# 2021_ZT_1.net
KiCad netlist of a schematic drawn in EasyEDA Pro
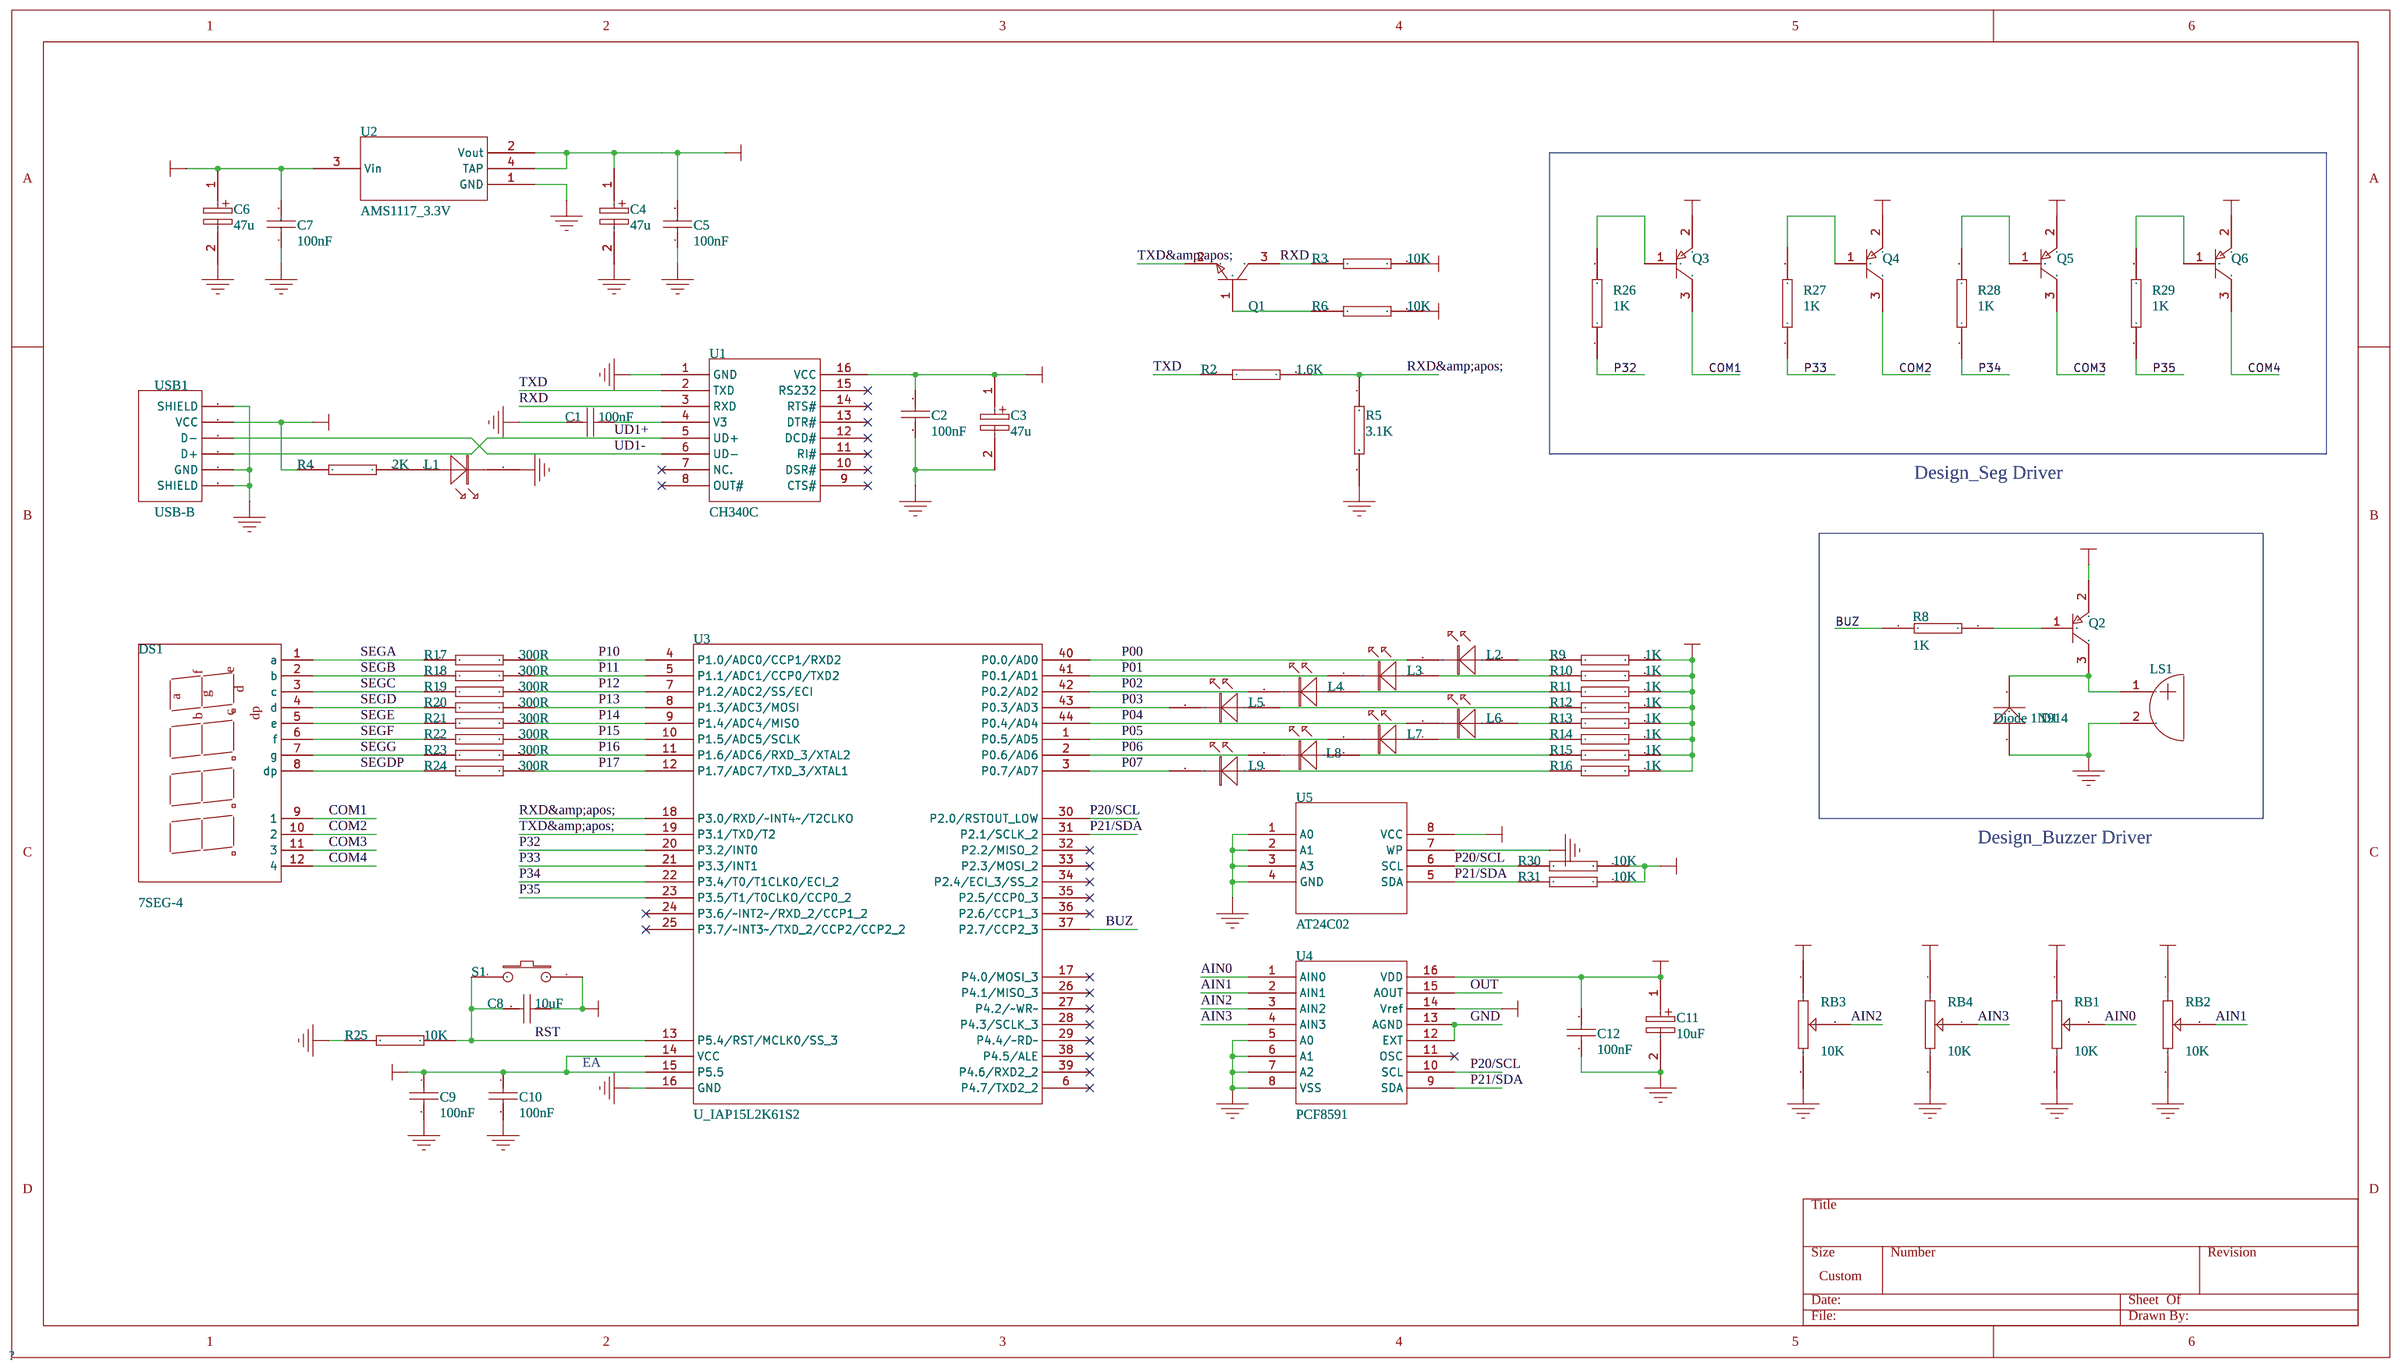
[diagram p0: schematic sheet]

(export (version "E")
  (design (tool "Eeschema 10.0.6"))
  (components
    (comp (ref "C1") (value "100nF") (libsource (lib "easyedapro") (part "CAP")))
    (comp (ref "C2") (value "100nF") (libsource (lib "easyedapro") (part "CAP")))
    (comp (ref "C3")
      (value "47u")
      (description "Electrolytic Capacitor")
      (libsource (lib "easyedapro") (part "CAP-2"))
    )
    (comp (ref "C4")
      (value "47u")
      (description "Electrolytic Capacitor")
      (libsource (lib "easyedapro") (part "CAP-2"))
    )
    (comp (ref "C5") (value "100nF") (description "Capacitor") (libsource (lib "easyedapro") (part "C_CAP")))
    (comp (ref "C6")
      (value "47u")
      (description "Electrolytic Capacitor")
      (libsource (lib "easyedapro") (part "CAP-2"))
    )
    (comp (ref "C7") (value "100nF") (description "Capacitor") (libsource (lib "easyedapro") (part "C_CAP")))
    (comp (ref "C8") (value "10uF") (libsource (lib "easyedapro") (part "CAP")))
    (comp (ref "C9") (value "100nF") (libsource (lib "easyedapro") (part "CAP")))
    (comp (ref "C10") (value "100nF") (libsource (lib "easyedapro") (part "CAP")))
    (comp (ref "C11")
      (value "10uF")
      (description "Electrolytic Capacitor")
      (libsource (lib "easyedapro") (part "ELECTRO2"))
    )
    (comp (ref "C12") (value "100nF") (description "Capacitor") (libsource (lib "easyedapro") (part "CAP")))
    (comp (ref "D1")
      (value "Diode 1N914")
      (description "High Conductance Fast Diode")
      (libsource (lib "easyedapro") (part "Diode 1N914"))
    )
    (comp (ref "DS1")
      (value "7SEG-4")
      (description "4 Seven-Segment Display, Right Hand Decimal")
      (libsource (lib "easyedapro") (part "7SEG-4"))
    )
    (comp (ref "L1") (value "LED") (libsource (lib "easyedapro") (part "LED")))
    (comp (ref "L2") (value "LED") (libsource (lib "easyedapro") (part "LED")))
    (comp (ref "L3") (value "LED") (libsource (lib "easyedapro") (part "LED")))
    (comp (ref "L4") (value "LED") (libsource (lib "easyedapro") (part "LED")))
    (comp (ref "L5") (value "LED") (libsource (lib "easyedapro") (part "LED")))
    (comp (ref "L6") (value "LED") (libsource (lib "easyedapro") (part "LED")))
    (comp (ref "L7") (value "LED") (libsource (lib "easyedapro") (part "LED")))
    (comp (ref "L8") (value "LED") (libsource (lib "easyedapro") (part "LED")))
    (comp (ref "L9") (value "LED") (libsource (lib "easyedapro") (part "LED")))
    (comp (ref "LS1") (value "S_BUZZER") (libsource (lib "easyedapro") (part "S_BUZZER")))
    (comp (ref "Q1")
      (value "8050-SOT23")
      (description "PNP-S8050")
      (libsource (lib "easyedapro") (part "Q_NPN"))
    )
    (comp (ref "Q2")
      (value "2N3906")
      (description "PNP General Purpose Amplifier")
      (libsource (lib "easyedapro") (part "2N3906"))
    )
    (comp (ref "Q3")
      (value "2N3906")
      (description "PNP General Purpose Amplifier")
      (libsource (lib "easyedapro") (part "2N3906"))
    )
    (comp (ref "Q4")
      (value "2N3906")
      (description "PNP General Purpose Amplifier")
      (libsource (lib "easyedapro") (part "2N3906"))
    )
    (comp (ref "Q5")
      (value "2N3906")
      (description "PNP General Purpose Amplifier")
      (libsource (lib "easyedapro") (part "2N3906"))
    )
    (comp (ref "Q6")
      (value "2N3906")
      (description "PNP General Purpose Amplifier")
      (libsource (lib "easyedapro") (part "2N3906"))
    )
    (comp (ref "R2") (value "1.6K") (libsource (lib "easyedapro") (part "RES2")))
    (comp (ref "R3") (value "10K") (libsource (lib "easyedapro") (part "RES2")))
    (comp (ref "R4") (value "2K") (libsource (lib "easyedapro") (part "RES2")))
    (comp (ref "R5") (value "3.1K") (libsource (lib "easyedapro") (part "RES2")))
    (comp (ref "R6") (value "10K") (libsource (lib "easyedapro") (part "RES2")))
    (comp (ref "R8") (value "1K") (libsource (lib "easyedapro") (part "RES2")))
    (comp (ref "R9") (value "1K") (libsource (lib "easyedapro") (part "RES2")))
    (comp (ref "R10") (value "1K") (libsource (lib "easyedapro") (part "RES2")))
    (comp (ref "R11") (value "1K") (libsource (lib "easyedapro") (part "RES2")))
    (comp (ref "R12") (value "1K") (libsource (lib "easyedapro") (part "RES2")))
    (comp (ref "R13") (value "1K") (libsource (lib "easyedapro") (part "RES2")))
    (comp (ref "R14") (value "1K") (libsource (lib "easyedapro") (part "RES2")))
    (comp (ref "R15") (value "1K") (libsource (lib "easyedapro") (part "RES2")))
    (comp (ref "R16") (value "1K") (libsource (lib "easyedapro") (part "RES2")))
    (comp (ref "R17") (value "300R") (libsource (lib "easyedapro") (part "RES2")))
    (comp (ref "R18") (value "300R") (libsource (lib "easyedapro") (part "RES2")))
    (comp (ref "R19") (value "300R") (libsource (lib "easyedapro") (part "RES2")))
    (comp (ref "R20") (value "300R") (libsource (lib "easyedapro") (part "RES2")))
    (comp (ref "R21") (value "300R") (libsource (lib "easyedapro") (part "RES2")))
    (comp (ref "R22") (value "300R") (libsource (lib "easyedapro") (part "RES2")))
    (comp (ref "R23") (value "300R") (libsource (lib "easyedapro") (part "RES2")))
    (comp (ref "R24") (value "300R") (libsource (lib "easyedapro") (part "RES2")))
    (comp (ref "R25") (value "10K") (libsource (lib "easyedapro") (part "RES2")))
    (comp (ref "R26") (value "1K") (libsource (lib "easyedapro") (part "RES2")))
    (comp (ref "R27") (value "1K") (libsource (lib "easyedapro") (part "RES2")))
    (comp (ref "R28") (value "1K") (libsource (lib "easyedapro") (part "RES2")))
    (comp (ref "R29") (value "1K") (libsource (lib "easyedapro") (part "RES2")))
    (comp (ref "R30") (value "10K") (libsource (lib "easyedapro") (part "RES2")))
    (comp (ref "R31") (value "10K") (libsource (lib "easyedapro") (part "RES2")))
    (comp (ref "RB1")
      (value "10K")
      (description "Potentiometer")
      (libsource (lib "easyedapro") (part "POT2"))
    )
    (comp (ref "RB2")
      (value "10K")
      (description "Potentiometer")
      (libsource (lib "easyedapro") (part "POT2"))
    )
    (comp (ref "RB3")
      (value "10K")
      (description "Potentiometer")
      (libsource (lib "easyedapro") (part "POT2"))
    )
    (comp (ref "RB4")
      (value "10K")
      (description "Potentiometer")
      (libsource (lib "easyedapro") (part "POT2"))
    )
    (comp (ref "S1") (value "SW-PB") (libsource (lib "easyedapro") (part "SW-PB")))
    (comp (ref "U1") (value "CH340C") (libsource (lib "easyedapro") (part "CH340C")))
    (comp (ref "U2")
      (value "AMS1117_3.3V")
      (description "POWER")
      (libsource (lib "easyedapro") (part "U_ASM1117"))
    )
    (comp (ref "U3")
      (value "U_IAP15L2K61S2")
      (description "MCU")
      (libsource (lib "easyedapro") (part "U_IAP15F2K61S2"))
    )
    (comp (ref "U4") (value "PCF8591") (libsource (lib "easyedapro") (part "PCF8591")))
    (comp (ref "U5") (value "AT24C02") (libsource (lib "easyedapro") (part "AT24C02")))
    (comp (ref "USB1")
      (value "USB-B")
      (description "Connector")
      (libsource (lib "easyedapro") (part "USB_A"))
    )
  )
  (nets
    (net (code "1") (name "+3V3") (class "Default")
      (node (ref "C10") (pin "1") (pintype "input"))
      (node (ref "C11") (pin "1") (pinfunction "1_1") (pintype "input"))
      (node (ref "C12") (pin "2") (pintype "input"))
      (node (ref "C4") (pin "1") (pinfunction "1_1") (pintype "input"))
      (node (ref "C5") (pin "2") (pinfunction "2_2") (pintype "input"))
      (node (ref "C8") (pin "2") (pintype "input"))
      (node (ref "C9") (pin "1") (pintype "input"))
      (node (ref "Q2") (pin "2") (pinfunction "E_2") (pintype "input"))
      (node (ref "Q3") (pin "2") (pinfunction "E_2") (pintype "input"))
      (node (ref "Q4") (pin "2") (pinfunction "E_2") (pintype "input"))
      (node (ref "Q5") (pin "2") (pinfunction "E_2") (pintype "input"))
      (node (ref "Q6") (pin "2") (pinfunction "E_2") (pintype "input"))
      (node (ref "R10") (pin "2") (pinfunction "2_2") (pintype "input"))
      (node (ref "R11") (pin "2") (pinfunction "2_2") (pintype "input"))
      (node (ref "R12") (pin "2") (pinfunction "2_2") (pintype "input"))
      (node (ref "R13") (pin "2") (pinfunction "2_2") (pintype "input"))
      (node (ref "R14") (pin "2") (pinfunction "2_2") (pintype "input"))
      (node (ref "R15") (pin "2") (pinfunction "2_2") (pintype "input"))
      (node (ref "R16") (pin "2") (pinfunction "2_2") (pintype "input"))
      (node (ref "R30") (pin "1") (pinfunction "1_1") (pintype "input"))
      (node (ref "R31") (pin "1") (pinfunction "1_1") (pintype "input"))
      (node (ref "R6") (pin "1") (pinfunction "1_1") (pintype "input"))
      (node (ref "R9") (pin "2") (pinfunction "2_2") (pintype "input"))
      (node (ref "RB1") (pin "1") (pinfunction "1_1") (pintype "input"))
      (node (ref "RB2") (pin "1") (pinfunction "1_1") (pintype "input"))
      (node (ref "RB3") (pin "1") (pinfunction "1_1") (pintype "input"))
      (node (ref "RB4") (pin "1") (pinfunction "1_1") (pintype "input"))
      (node (ref "S1") (pin "2") (pinfunction "2_2") (pintype "input"))
      (node (ref "U2") (pin "2") (pinfunction "Vout_2") (pintype "input"))
      (node (ref "U2") (pin "4") (pinfunction "TAP_4") (pintype "input"))
      (node (ref "U3") (pin "14") (pinfunction "VCC_14") (pintype "input"))
      (node (ref "U3") (pin "15") (pinfunction "P5.5_15") (pintype "bidirectional"))
      (node (ref "U4") (pin "14") (pinfunction "Vref_14") (pintype "input"))
      (node (ref "U4") (pin "16") (pinfunction "VDD_16") (pintype "input"))
      (node (ref "U5") (pin "8") (pinfunction "VCC_8") (pintype "input"))
    )
    (net (code "2") (name "+5V") (class "Default")
      (node (ref "C2") (pin "1") (pintype "input"))
      (node (ref "C3") (pin "1") (pinfunction "1_1") (pintype "input"))
      (node (ref "C6") (pin "1") (pinfunction "1_1") (pintype "input"))
      (node (ref "C7") (pin "2") (pinfunction "2_2") (pintype "input"))
      (node (ref "R3") (pin "1") (pinfunction "1_1") (pintype "input"))
      (node (ref "R4") (pin "2") (pinfunction "2_2") (pintype "input"))
      (node (ref "U1") (pin "16") (pinfunction "VCC_16") (pintype "input"))
      (node (ref "U2") (pin "3") (pinfunction "Vin_3") (pintype "input"))
      (node (ref "USB1") (pin "1") (pinfunction "VCC_1") (pintype "input"))
    )
    (net (code "3") (name "/AIN0") (class "Default")
      (node (ref "RB1") (pin "2") (pinfunction "W_2") (pintype "input"))
      (node (ref "U4") (pin "1") (pinfunction "AIN0_1") (pintype "input"))
    )
    (net (code "4") (name "/AIN1") (class "Default")
      (node (ref "RB2") (pin "2") (pinfunction "W_2") (pintype "input"))
      (node (ref "U4") (pin "2") (pinfunction "AIN1_2") (pintype "input"))
    )
    (net (code "5") (name "/AIN2") (class "Default")
      (node (ref "RB3") (pin "2") (pinfunction "W_2") (pintype "input"))
      (node (ref "U4") (pin "3") (pinfunction "AIN2_3") (pintype "input"))
    )
    (net (code "6") (name "/AIN3") (class "Default")
      (node (ref "RB4") (pin "2") (pinfunction "W_2") (pintype "input"))
      (node (ref "U4") (pin "4") (pinfunction "AIN3_4") (pintype "input"))
    )
    (net (code "7") (name "/BUZ") (class "Default")
      (node (ref "R8") (pin "1") (pinfunction "1_1") (pintype "input"))
      (node (ref "U3") (pin "37") (pinfunction "P2.7/CCP2_3_37") (pintype "bidirectional"))
    )
    (net (code "8") (name "/COM1") (class "Default")
      (node (ref "DS1") (pin "9") (pinfunction "1_9") (pintype "input"))
      (node (ref "Q3") (pin "3") (pinfunction "C_3") (pintype "input"))
    )
    (net (code "9") (name "/COM2") (class "Default")
      (node (ref "DS1") (pin "10") (pinfunction "2_10") (pintype "input"))
      (node (ref "Q4") (pin "3") (pinfunction "C_3") (pintype "input"))
    )
    (net (code "10") (name "/COM3") (class "Default")
      (node (ref "DS1") (pin "11") (pinfunction "3_11") (pintype "input"))
      (node (ref "Q5") (pin "3") (pinfunction "C_3") (pintype "input"))
    )
    (net (code "11") (name "/COM4") (class "Default")
      (node (ref "DS1") (pin "12") (pinfunction "4_12") (pintype "input"))
      (node (ref "Q6") (pin "3") (pinfunction "C_3") (pintype "input"))
    )
    (net (code "12") (name "/OUT") (class "Default")
      (node (ref "U4") (pin "15") (pinfunction "AOUT_15") (pintype "input"))
    )
    (net (code "13") (name "/P00") (class "Default")
      (node (ref "L2") (pin "2") (pinfunction "K_2") (pintype "input"))
      (node (ref "U3") (pin "40") (pinfunction "P0.0/AD0_40") (pintype "bidirectional"))
    )
    (net (code "14") (name "/P01") (class "Default")
      (node (ref "L3") (pin "2") (pinfunction "K_2") (pintype "input"))
      (node (ref "U3") (pin "41") (pinfunction "P0.1/AD1_41") (pintype "bidirectional"))
    )
    (net (code "15") (name "/P02") (class "Default")
      (node (ref "L4") (pin "2") (pinfunction "K_2") (pintype "input"))
      (node (ref "U3") (pin "42") (pinfunction "P0.2/AD2_42") (pintype "bidirectional"))
    )
    (net (code "16") (name "/P03") (class "Default")
      (node (ref "L5") (pin "2") (pinfunction "K_2") (pintype "input"))
      (node (ref "U3") (pin "43") (pinfunction "P0.3/AD3_43") (pintype "bidirectional"))
    )
    (net (code "17") (name "/P04") (class "Default")
      (node (ref "L6") (pin "2") (pinfunction "K_2") (pintype "input"))
      (node (ref "U3") (pin "44") (pinfunction "P0.4/AD4_44") (pintype "bidirectional"))
    )
    (net (code "18") (name "/P05") (class "Default")
      (node (ref "L7") (pin "2") (pinfunction "K_2") (pintype "input"))
      (node (ref "U3") (pin "1") (pinfunction "P0.5/AD5_1") (pintype "bidirectional"))
    )
    (net (code "19") (name "/P06") (class "Default")
      (node (ref "L8") (pin "2") (pinfunction "K_2") (pintype "input"))
      (node (ref "U3") (pin "2") (pinfunction "P0.6/AD6_2") (pintype "bidirectional"))
    )
    (net (code "20") (name "/P07") (class "Default")
      (node (ref "L9") (pin "2") (pinfunction "K_2") (pintype "input"))
      (node (ref "U3") (pin "3") (pinfunction "P0.7/AD7_3") (pintype "bidirectional"))
    )
    (net (code "21") (name "/P10") (class "Default")
      (node (ref "R17") (pin "2") (pinfunction "2_2") (pintype "input"))
      (node (ref "U3") (pin "4") (pinfunction "P1.0/ADC0/CCP1/RXD2_4") (pintype "input"))
    )
    (net (code "22") (name "/P11") (class "Default")
      (node (ref "R18") (pin "2") (pinfunction "2_2") (pintype "input"))
      (node (ref "U3") (pin "5") (pinfunction "P1.1/ADC1/CCP0/TXD2_5") (pintype "input"))
    )
    (net (code "23") (name "/P12") (class "Default")
      (node (ref "R19") (pin "2") (pinfunction "2_2") (pintype "input"))
      (node (ref "U3") (pin "7") (pinfunction "P1.2/ADC2/SS/ECI_7") (pintype "input"))
    )
    (net (code "24") (name "/P13") (class "Default")
      (node (ref "R20") (pin "2") (pinfunction "2_2") (pintype "input"))
      (node (ref "U3") (pin "8") (pinfunction "P1.3/ADC3/MOSI_8") (pintype "input"))
    )
    (net (code "25") (name "/P14") (class "Default")
      (node (ref "R21") (pin "2") (pinfunction "2_2") (pintype "input"))
      (node (ref "U3") (pin "9") (pinfunction "P1.4/ADC4/MISO_9") (pintype "input"))
    )
    (net (code "26") (name "/P15") (class "Default")
      (node (ref "R22") (pin "2") (pinfunction "2_2") (pintype "input"))
      (node (ref "U3") (pin "10") (pinfunction "P1.5/ADC5/SCLK_10") (pintype "input"))
    )
    (net (code "27") (name "/P16") (class "Default")
      (node (ref "R23") (pin "2") (pinfunction "2_2") (pintype "input"))
      (node (ref "U3") (pin "11") (pinfunction "P1.6/ADC6/RXD_3/XTAL2_11") (pintype "bidirectional"))
    )
    (net (code "28") (name "/P17") (class "Default")
      (node (ref "R24") (pin "2") (pinfunction "2_2") (pintype "input"))
      (node (ref "U3") (pin "12") (pinfunction "P1.7/ADC7/TXD_3/XTAL1_12") (pintype "bidirectional"))
    )
    (net (code "29") (name "/P20{slash}SCL") (class "Default")
      (node (ref "R30") (pin "2") (pinfunction "2_2") (pintype "input"))
      (node (ref "U3") (pin "30") (pinfunction "P2.0/RSTOUT_LOW_30") (pintype "bidirectional"))
      (node (ref "U4") (pin "10") (pinfunction "SCL_10") (pintype "input"))
      (node (ref "U5") (pin "6") (pinfunction "SCL_6") (pintype "input"))
    )
    (net (code "30") (name "/P21{slash}SDA") (class "Default")
      (node (ref "R31") (pin "2") (pinfunction "2_2") (pintype "input"))
      (node (ref "U3") (pin "31") (pinfunction "P2.1/SCLK_2_31") (pintype "bidirectional"))
      (node (ref "U4") (pin "9") (pinfunction "SDA_9") (pintype "input"))
      (node (ref "U5") (pin "5") (pinfunction "SDA_5") (pintype "input"))
    )
    (net (code "31") (name "/P32") (class "Default")
      (node (ref "R26") (pin "1") (pinfunction "1_1") (pintype "input"))
      (node (ref "U3") (pin "20") (pinfunction "P3.2/INT0_20") (pintype "input"))
    )
    (net (code "32") (name "/P33") (class "Default")
      (node (ref "R27") (pin "1") (pinfunction "1_1") (pintype "input"))
      (node (ref "U3") (pin "21") (pinfunction "P3.3/INT1_21") (pintype "input"))
    )
    (net (code "33") (name "/P34") (class "Default")
      (node (ref "R28") (pin "1") (pinfunction "1_1") (pintype "input"))
      (node (ref "U3") (pin "22") (pinfunction "P3.4/T0/T1CLKO/ECI_2_22") (pintype "bidirectional"))
    )
    (net (code "34") (name "/P35") (class "Default")
      (node (ref "R29") (pin "1") (pinfunction "1_1") (pintype "input"))
      (node (ref "U3") (pin "23") (pinfunction "P3.5/T1/T0CLKO/CCP0_2_23") (pintype "input"))
    )
    (net (code "35") (name "/RST") (class "Default")
      (node (ref "C8") (pin "1") (pintype "input"))
      (node (ref "R25") (pin "1") (pinfunction "1_1") (pintype "input"))
      (node (ref "S1") (pin "1") (pinfunction "1_1") (pintype "input"))
      (node (ref "U3") (pin "13") (pinfunction "P5.4/RST/MCLK0/SS_3_13") (pintype "bidirectional"))
    )
    (net (code "36") (name "/RXD") (class "Default")
      (node (ref "Q1") (pin "3") (pinfunction "C_3") (pintype "input"))
      (node (ref "R3") (pin "2") (pinfunction "2_2") (pintype "input"))
      (node (ref "U1") (pin "3") (pinfunction "RXD_3") (pintype "input"))
    )
    (net (code "37") (name "/RXD&amp;apos;") (class "Default")
      (node (ref "R2") (pin "1") (pinfunction "1_1") (pintype "input"))
      (node (ref "R5") (pin "1") (pinfunction "1_1") (pintype "input"))
      (node (ref "U3") (pin "18") (pinfunction "P3.0/RXD/~INT4~/T2CLKO_18") (pintype "input"))
    )
    (net (code "38") (name "/SEGA") (class "Default")
      (node (ref "DS1") (pin "1") (pinfunction "a_1") (pintype "input"))
      (node (ref "R17") (pin "1") (pinfunction "1_1") (pintype "input"))
    )
    (net (code "39") (name "/SEGB") (class "Default")
      (node (ref "DS1") (pin "2") (pinfunction "b_2") (pintype "input"))
      (node (ref "R18") (pin "1") (pinfunction "1_1") (pintype "input"))
    )
    (net (code "40") (name "/SEGC") (class "Default")
      (node (ref "DS1") (pin "3") (pinfunction "c_3") (pintype "input"))
      (node (ref "R19") (pin "1") (pinfunction "1_1") (pintype "input"))
    )
    (net (code "41") (name "/SEGD") (class "Default")
      (node (ref "DS1") (pin "4") (pinfunction "d_4") (pintype "input"))
      (node (ref "R20") (pin "1") (pinfunction "1_1") (pintype "input"))
    )
    (net (code "42") (name "/SEGDP") (class "Default")
      (node (ref "DS1") (pin "8") (pinfunction "dp_8") (pintype "input"))
      (node (ref "R24") (pin "1") (pinfunction "1_1") (pintype "input"))
    )
    (net (code "43") (name "/SEGE") (class "Default")
      (node (ref "DS1") (pin "5") (pinfunction "e_5") (pintype "input"))
      (node (ref "R21") (pin "1") (pinfunction "1_1") (pintype "input"))
    )
    (net (code "44") (name "/SEGF") (class "Default")
      (node (ref "DS1") (pin "6") (pinfunction "f_6") (pintype "input"))
      (node (ref "R22") (pin "1") (pinfunction "1_1") (pintype "input"))
    )
    (net (code "45") (name "/SEGG") (class "Default")
      (node (ref "DS1") (pin "7") (pinfunction "g_7") (pintype "input"))
      (node (ref "R23") (pin "1") (pinfunction "1_1") (pintype "input"))
    )
    (net (code "46") (name "/TXD") (class "Default")
      (node (ref "R2") (pin "2") (pinfunction "2_2") (pintype "input"))
      (node (ref "U1") (pin "2") (pinfunction "TXD_2") (pintype "input"))
    )
    (net (code "47") (name "/TXD&amp;apos;") (class "Default")
      (node (ref "Q1") (pin "2") (pinfunction "E_2") (pintype "input"))
      (node (ref "U3") (pin "19") (pinfunction "P3.1/TXD/T2_19") (pintype "input"))
    )
    (net (code "48") (name "/UD1+") (class "Default")
      (node (ref "U1") (pin "5") (pinfunction "UD+_5") (pintype "input"))
      (node (ref "USB1") (pin "3") (pinfunction "D+_3") (pintype "input"))
    )
    (net (code "49") (name "/UD1-") (class "Default")
      (node (ref "U1") (pin "6") (pinfunction "UD-_6") (pintype "input"))
      (node (ref "USB1") (pin "2") (pinfunction "D-_2") (pintype "input"))
    )
    (net (code "50") (name "GND") (class "Default")
      (node (ref "C1") (pin "1") (pintype "input"))
      (node (ref "C10") (pin "2") (pintype "input"))
      (node (ref "C11") (pin "2") (pinfunction "2_2") (pintype "input"))
      (node (ref "C12") (pin "1") (pintype "input"))
      (node (ref "C2") (pin "2") (pintype "input"))
      (node (ref "C3") (pin "2") (pinfunction "2_2") (pintype "input"))
      (node (ref "C4") (pin "2") (pinfunction "2_2") (pintype "input"))
      (node (ref "C5") (pin "1") (pinfunction "1_1") (pintype "input"))
      (node (ref "C6") (pin "2") (pinfunction "2_2") (pintype "input"))
      (node (ref "C7") (pin "1") (pinfunction "1_1") (pintype "input"))
      (node (ref "C9") (pin "2") (pintype "input"))
      (node (ref "D1") (pin "1") (pinfunction "A_1") (pintype "input"))
      (node (ref "L1") (pin "2") (pinfunction "K_2") (pintype "input"))
      (node (ref "LS1") (pin "2") (pinfunction "2_2") (pintype "input"))
      (node (ref "R25") (pin "2") (pinfunction "2_2") (pintype "input"))
      (node (ref "R5") (pin "2") (pinfunction "2_2") (pintype "input"))
      (node (ref "RB1") (pin "3") (pinfunction "2_3") (pintype "input"))
      (node (ref "RB2") (pin "3") (pinfunction "2_3") (pintype "input"))
      (node (ref "RB3") (pin "3") (pinfunction "2_3") (pintype "input"))
      (node (ref "RB4") (pin "3") (pinfunction "2_3") (pintype "input"))
      (node (ref "U1") (pin "1") (pinfunction "GND_1") (pintype "input"))
      (node (ref "U2") (pin "1") (pinfunction "GND_1") (pintype "input"))
      (node (ref "U3") (pin "16") (pinfunction "GND_16") (pintype "input"))
      (node (ref "U4") (pin "12") (pinfunction "EXT_12") (pintype "input"))
      (node (ref "U4") (pin "13") (pinfunction "AGND_13") (pintype "input"))
      (node (ref "U4") (pin "5") (pinfunction "A0_5") (pintype "input"))
      (node (ref "U4") (pin "6") (pinfunction "A1_6") (pintype "input"))
      (node (ref "U4") (pin "7") (pinfunction "A2_7") (pintype "input"))
      (node (ref "U4") (pin "8") (pinfunction "VSS_8") (pintype "input"))
      (node (ref "U5") (pin "1") (pinfunction "A0_1") (pintype "input"))
      (node (ref "U5") (pin "2") (pinfunction "A1_2") (pintype "input"))
      (node (ref "U5") (pin "3") (pinfunction "A3_3") (pintype "input"))
      (node (ref "U5") (pin "4") (pinfunction "GND_4") (pintype "input"))
      (node (ref "U5") (pin "7") (pinfunction "WP_7") (pintype "input"))
      (node (ref "USB1") (pin "4") (pinfunction "GND_4") (pintype "input"))
      (node (ref "USB1") (pin "5") (pinfunction "SHIELD_5") (pintype "input"))
      (node (ref "USB1") (pin "6") (pinfunction "SHIELD_6") (pintype "input"))
    )
    (net (code "51") (name "Net-(D1-K)") (class "Default")
      (node (ref "D1") (pin "2") (pinfunction "K_2") (pintype "input"))
      (node (ref "LS1") (pin "1") (pinfunction "1_1") (pintype "input"))
      (node (ref "Q2") (pin "3") (pinfunction "C_3") (pintype "input"))
    )
    (net (code "52") (name "Net-(L1-A)") (class "Default")
      (node (ref "L1") (pin "1") (pinfunction "A_1") (pintype "input"))
      (node (ref "R4") (pin "1") (pinfunction "1_1") (pintype "input"))
    )
    (net (code "53") (name "Net-(L2-A)") (class "Default")
      (node (ref "L2") (pin "1") (pinfunction "A_1") (pintype "input"))
      (node (ref "R9") (pin "1") (pinfunction "1_1") (pintype "input"))
    )
    (net (code "54") (name "Net-(L3-A)") (class "Default")
      (node (ref "L3") (pin "1") (pinfunction "A_1") (pintype "input"))
      (node (ref "R10") (pin "1") (pinfunction "1_1") (pintype "input"))
    )
    (net (code "55") (name "Net-(L4-A)") (class "Default")
      (node (ref "L4") (pin "1") (pinfunction "A_1") (pintype "input"))
      (node (ref "R11") (pin "1") (pinfunction "1_1") (pintype "input"))
    )
    (net (code "56") (name "Net-(L5-A)") (class "Default")
      (node (ref "L5") (pin "1") (pinfunction "A_1") (pintype "input"))
      (node (ref "R12") (pin "1") (pinfunction "1_1") (pintype "input"))
    )
    (net (code "57") (name "Net-(L6-A)") (class "Default")
      (node (ref "L6") (pin "1") (pinfunction "A_1") (pintype "input"))
      (node (ref "R13") (pin "1") (pinfunction "1_1") (pintype "input"))
    )
    (net (code "58") (name "Net-(L7-A)") (class "Default")
      (node (ref "L7") (pin "1") (pinfunction "A_1") (pintype "input"))
      (node (ref "R14") (pin "1") (pinfunction "1_1") (pintype "input"))
    )
    (net (code "59") (name "Net-(L8-A)") (class "Default")
      (node (ref "L8") (pin "1") (pinfunction "A_1") (pintype "input"))
      (node (ref "R15") (pin "1") (pinfunction "1_1") (pintype "input"))
    )
    (net (code "60") (name "Net-(L9-A)") (class "Default")
      (node (ref "L9") (pin "1") (pinfunction "A_1") (pintype "input"))
      (node (ref "R16") (pin "1") (pinfunction "1_1") (pintype "input"))
    )
    (net (code "61") (name "Net-(Q1-B)") (class "Default")
      (node (ref "Q1") (pin "1") (pinfunction "B_1") (pintype "input"))
      (node (ref "R6") (pin "2") (pinfunction "2_2") (pintype "input"))
    )
    (net (code "62") (name "Net-(Q2-B)") (class "Default")
      (node (ref "Q2") (pin "1") (pinfunction "B_1") (pintype "input"))
      (node (ref "R8") (pin "2") (pinfunction "2_2") (pintype "input"))
    )
    (net (code "63") (name "Net-(Q3-B)") (class "Default")
      (node (ref "Q3") (pin "1") (pinfunction "B_1") (pintype "input"))
      (node (ref "R26") (pin "2") (pinfunction "2_2") (pintype "input"))
    )
    (net (code "64") (name "Net-(Q4-B)") (class "Default")
      (node (ref "Q4") (pin "1") (pinfunction "B_1") (pintype "input"))
      (node (ref "R27") (pin "2") (pinfunction "2_2") (pintype "input"))
    )
    (net (code "65") (name "Net-(Q5-B)") (class "Default")
      (node (ref "Q5") (pin "1") (pinfunction "B_1") (pintype "input"))
      (node (ref "R28") (pin "2") (pinfunction "2_2") (pintype "input"))
    )
    (net (code "66") (name "Net-(Q6-B)") (class "Default")
      (node (ref "Q6") (pin "1") (pinfunction "B_1") (pintype "input"))
      (node (ref "R29") (pin "2") (pinfunction "2_2") (pintype "input"))
    )
    (net (code "67") (name "Net-(U1-V3)") (class "Default")
      (node (ref "C1") (pin "2") (pintype "input"))
      (node (ref "U1") (pin "4") (pinfunction "V3_4") (pintype "input"))
    )
    (net (code "68") (name "unconnected-(U1-CTS#-Pad9)") (class "Default")
      (node (ref "U1") (pin "9") (pinfunction "CTS#_9") (pintype "input+no_connect"))
    )
    (net (code "69") (name "unconnected-(U1-DCD#-Pad12)") (class "Default")
      (node (ref "U1") (pin "12") (pinfunction "DCD#_12") (pintype "input+no_connect"))
    )
    (net (code "70") (name "unconnected-(U1-DSR#-Pad10)") (class "Default")
      (node (ref "U1") (pin "10") (pinfunction "DSR#_10") (pintype "input+no_connect"))
    )
    (net (code "71") (name "unconnected-(U1-DTR#-Pad13)") (class "Default")
      (node (ref "U1") (pin "13") (pinfunction "DTR#_13") (pintype "input+no_connect"))
    )
    (net (code "72") (name "unconnected-(U1-NC.-Pad7)") (class "Default")
      (node (ref "U1") (pin "7") (pinfunction "NC._7") (pintype "input+no_connect"))
    )
    (net (code "73") (name "unconnected-(U1-OUT#-Pad8)") (class "Default")
      (node (ref "U1") (pin "8") (pinfunction "OUT#_8") (pintype "input+no_connect"))
    )
    (net (code "74") (name "unconnected-(U1-RI#-Pad11)") (class "Default")
      (node (ref "U1") (pin "11") (pinfunction "RI#_11") (pintype "input+no_connect"))
    )
    (net (code "75") (name "unconnected-(U1-RS232-Pad15)") (class "Default")
      (node (ref "U1") (pin "15") (pinfunction "RS232_15") (pintype "input+no_connect"))
    )
    (net (code "76") (name "unconnected-(U1-RTS#-Pad14)") (class "Default")
      (node (ref "U1") (pin "14") (pinfunction "RTS#_14") (pintype "input+no_connect"))
    )
    (net (code "77") (name "unconnected-(U3-P2.2{slash}MISO_2-Pad32)") (class "Default")
      (node (ref "U3") (pin "32") (pinfunction "P2.2/MISO_2_32") (pintype "bidirectional+no_connect"))
    )
    (net (code "78") (name "unconnected-(U3-P2.3{slash}MOSI_2-Pad33)") (class "Default")
      (node (ref "U3") (pin "33") (pinfunction "P2.3/MOSI_2_33") (pintype "bidirectional+no_connect"))
    )
    (net (code "79") (name "unconnected-(U3-P2.4{slash}ECI_3{slash}SS_2-Pad34)") (class "Default")
      (node (ref "U3") (pin "34") (pinfunction "P2.4/ECI_3/SS_2_34") (pintype "bidirectional+no_connect"))
    )
    (net (code "80") (name "unconnected-(U3-P2.5{slash}CCP0_3-Pad35)") (class "Default")
      (node (ref "U3") (pin "35") (pinfunction "P2.5/CCP0_3_35") (pintype "bidirectional+no_connect"))
    )
    (net (code "81") (name "unconnected-(U3-P2.6{slash}CCP1_3-Pad36)") (class "Default")
      (node (ref "U3") (pin "36") (pinfunction "P2.6/CCP1_3_36") (pintype "bidirectional+no_connect"))
    )
    (net (code "82") (name "unconnected-(U3-P3.6{slash}~INT2~{slash}RXD_2{slash}CCP1_2-Pad24)") (class "Default")
      (node (ref "U3") (pin "24") (pinfunction "P3.6/~INT2~/RXD_2/CCP1_2_24") (pintype "input+no_connect"))
    )
    (net (code "83") (name "unconnected-(U3-P3.7{slash}~INT3~{slash}TXD_2{slash}CCP2{slash}CCP2_2-Pad25)") (class "Default")
      (node (ref "U3") (pin "25") (pinfunction "P3.7/~INT3~/TXD_2/CCP2/CCP2_2_25") (pintype "input+no_connect"))
    )
    (net (code "84") (name "unconnected-(U3-P4.0{slash}MOSI_3-Pad17)") (class "Default")
      (node (ref "U3") (pin "17") (pinfunction "P4.0/MOSI_3_17") (pintype "bidirectional+no_connect"))
    )
    (net (code "85") (name "unconnected-(U3-P4.1{slash}MISO_3-Pad26)") (class "Default")
      (node (ref "U3") (pin "26") (pinfunction "P4.1/MISO_3_26") (pintype "bidirectional+no_connect"))
    )
    (net (code "86") (name "unconnected-(U3-P4.2{slash}~WR~-Pad27)") (class "Default")
      (node (ref "U3") (pin "27") (pinfunction "P4.2/~WR~_27") (pintype "input+no_connect"))
    )
    (net (code "87") (name "unconnected-(U3-P4.3{slash}SCLK_3-Pad28)") (class "Default")
      (node (ref "U3") (pin "28") (pinfunction "P4.3/SCLK_3_28") (pintype "bidirectional+no_connect"))
    )
    (net (code "88") (name "unconnected-(U3-P4.4{slash}~RD~-Pad29)") (class "Default")
      (node (ref "U3") (pin "29") (pinfunction "P4.4/~RD~_29") (pintype "input+no_connect"))
    )
    (net (code "89") (name "unconnected-(U3-P4.5{slash}ALE-Pad38)") (class "Default")
      (node (ref "U3") (pin "38") (pinfunction "P4.5/ALE_38") (pintype "input+no_connect"))
    )
    (net (code "90") (name "unconnected-(U3-P4.6{slash}RXD2_2-Pad39)") (class "Default")
      (node (ref "U3") (pin "39") (pinfunction "P4.6/RXD2_2_39") (pintype "input+no_connect"))
    )
    (net (code "91") (name "unconnected-(U3-P4.7{slash}TXD2_2-Pad6)") (class "Default")
      (node (ref "U3") (pin "6") (pinfunction "P4.7/TXD2_2_6") (pintype "bidirectional+no_connect"))
    )
    (net (code "92") (name "unconnected-(U4-OSC-Pad11)") (class "Default")
      (node (ref "U4") (pin "11") (pinfunction "OSC_11") (pintype "input+no_connect"))
    )
  )
)
